# nfc-epd-afe.net
KiCad netlist of a schematic drawn in Altium Designer
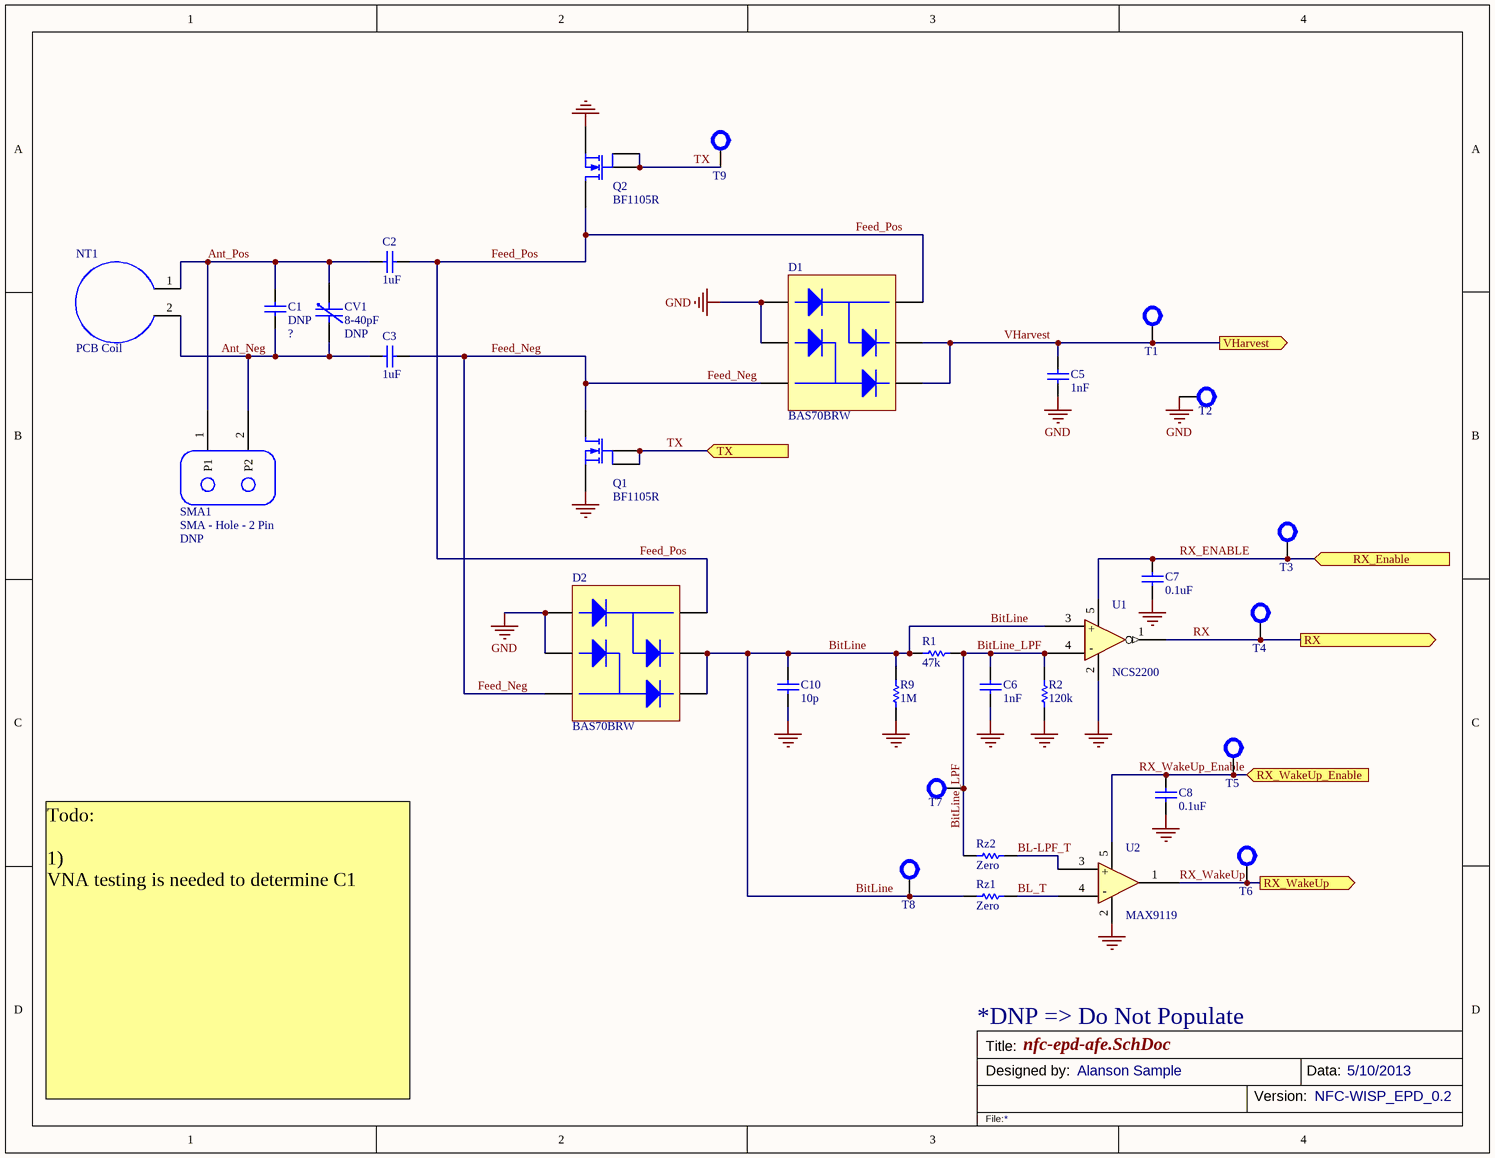
[diagram p0: nfc-epd-afe.SchDoc]

(export (version "E")
  (design (tool "Eeschema 10.0.6"))
  (components
    (comp (ref "C1")
      (value "?")
      (footprint "0603")
      (description "Ceramic Capacitor (Surface Mount)")
      (fields
        (field (name "MANUFACTURER") "Generic Ceramic Chip Cap (TBD)")
        (field (name "NOTE") "DNP")
        (field (name "Comment") "Cap")
      )
      (libsource (lib "WISP_AD10") (part "Cap"))
    )
    (comp (ref "C2")
      (value "1uF")
      (footprint "0603")
      (description "Ceramic Capacitor (Surface Mount)")
      (fields (field (name "MANUFACTURER") "Generic Ceramic Chip Cap (TBD)") (field (name "Comment") "Cap"))
      (libsource (lib "WISP_AD10") (part "Cap"))
    )
    (comp (ref "C3")
      (value "1uF")
      (footprint "0603")
      (description "Ceramic Capacitor (Surface Mount)")
      (fields (field (name "MANUFACTURER") "Generic Ceramic Chip Cap (TBD)") (field (name "Comment") "Cap"))
      (libsource (lib "WISP_AD10") (part "Cap"))
    )
    (comp (ref "C5")
      (value "1nF")
      (footprint "0603")
      (description "Ceramic Capacitor (Surface Mount)")
      (fields (field (name "MANUFACTURER") "Generic Ceramic Chip Cap (TBD)") (field (name "Comment") "Cap"))
      (libsource (lib "WISP_AD10") (part "Cap"))
    )
    (comp (ref "C6")
      (value "1nF")
      (footprint "0603")
      (description "Ceramic Capacitor (Surface Mount)")
      (fields (field (name "MANUFACTURER") "Generic Ceramic Chip Cap (TBD)") (field (name "Comment") "Cap"))
      (libsource (lib "WISP_AD10") (part "Cap"))
    )
    (comp (ref "C7")
      (value "0.1uF")
      (footprint "0603")
      (description "Ceramic Capacitor (Surface Mount)")
      (fields (field (name "MANUFACTURER") "Generic Ceramic Chip Cap (TBD)") (field (name "Comment") "Cap"))
      (libsource (lib "WISP_AD10") (part "Cap"))
    )
    (comp (ref "C8")
      (value "0.1uF")
      (footprint "0603")
      (description "Ceramic Capacitor (Surface Mount)")
      (fields (field (name "MANUFACTURER") "Generic Ceramic Chip Cap (TBD)") (field (name "Comment") "Cap"))
      (libsource (lib "WISP_AD10") (part "Cap"))
    )
    (comp (ref "C10")
      (value "10p")
      (footprint "0603")
      (description "Ceramic Capacitor (Surface Mount)")
      (fields (field (name "MANUFACTURER") "Generic Ceramic Chip Cap (TBD)") (field (name "Comment") "Cap"))
      (libsource (lib "WISP_AD10") (part "Cap"))
    )
    (comp (ref "CV1")
      (value "8-40pF")
      (footprint "Var-Cap - GKY40056")
      (description "Var-Cap Sprague-Goodman GKY40056")
      (fields
        (field (name "DIGI-KEY PART NUMBER") "SG9013CT-ND")
        (field (name "MANUFACTURER PART NUMBER") "GKY40056")
        (field (name "NOTES") "DNP")
      )
      (libsource (lib "WISP_AD10") (part "Var-Cap/603"))
    )
    (comp (ref "D1")
      (value "BAS70BRW")
      (footprint "SOT-363")
      (description "Diode Array - 2 Pair Series Connection")
      (fields
        (field (name "MANUFACTURER") "Diodes Inc")
        (field (name "MANUFACTURER PART NUMBER") "BAS70BRW-7-F")
      )
      (libsource (lib "WISP_AD10") (part "Diode - Array_2"))
    )
    (comp (ref "D2")
      (value "BAS70BRW")
      (footprint "SOT-363")
      (description "Diode Array - 2 Pair Series Connection")
      (fields
        (field (name "MANUFACTURER") "Diodes Inc")
        (field (name "MANUFACTURER PART NUMBER") "BAS70BRW-7-F")
      )
      (libsource (lib "WISP_AD10") (part "Diode - Array_2"))
    )
    (comp (ref "NT1")
      (value "PCB Coil")
      (footprint "Net Tie - 50mil")
      (description "Hand draw coil symbol based on a 'Net Tie'")
      (libsource (lib "WISP_AD10") (part "Net Tie - Coil"))
    )
    (comp (ref "Q1")
      (value "BF1105R")
      (footprint "SOT-143R")
      (description "SOT-143R, N-Channel Dual-Gate Mos-Fets MOSFET")
      (fields
        (field (name "DIGI-KEY PART NUMBER") "BF1105R,215-ND")
        (field (name "MANUFACTURER PART NUMBER") "BF1105R,215")
      )
      (libsource (lib "WISP_AD10") (part "BF1105R"))
    )
    (comp (ref "Q2")
      (value "BF1105R")
      (footprint "SOT-143R")
      (description "SOT-143R, N-Channel Dual-Gate Mos-Fets MOSFET")
      (fields
        (field (name "DIGI-KEY PART NUMBER") "BF1105R,215-ND")
        (field (name "MANUFACTURER PART NUMBER") "BF1105R,215")
      )
      (libsource (lib "WISP_AD10") (part "BF1105R"))
    )
    (comp (ref "R1")
      (value "47k")
      (footprint "0603")
      (description "Chip Resistor (Surface Mount)")
      (fields (field (name "MANUFACTURER") "Generic Chip Res (TBD)") (field (name "Comment") "Res"))
      (libsource (lib "WISP_AD10") (part "Res"))
    )
    (comp (ref "R2")
      (value "120k")
      (footprint "0603")
      (description "Chip Resistor (Surface Mount)")
      (fields (field (name "MANUFACTURER") "Generic Chip Res (TBD)") (field (name "Comment") "Res"))
      (libsource (lib "WISP_AD10") (part "Res"))
    )
    (comp (ref "R9")
      (value "1M")
      (footprint "0603")
      (description "Chip Resistor (Surface Mount)")
      (fields (field (name "MANUFACTURER") "Generic Chip Res (TBD)") (field (name "Comment") "Res"))
      (libsource (lib "WISP_AD10") (part "Res"))
    )
    (comp (ref "Rz1")
      (value "Zero")
      (footprint "0603")
      (description "Chip Resistor (Surface Mount)")
      (fields (field (name "MANUFACTURER") "Generic Chip Res (TBD)") (field (name "Comment") "Res"))
      (libsource (lib "WREL_AD10") (part "Res"))
    )
    (comp (ref "Rz2")
      (value "Zero")
      (footprint "0603")
      (description "Chip Resistor (Surface Mount)")
      (fields (field (name "MANUFACTURER") "Generic Chip Res (TBD)") (field (name "Comment") "Res"))
      (libsource (lib "WREL_AD10") (part "Res"))
    )
    (comp (ref "SMA1")
      (value "SMA - Hole - 2 Pin")
      (footprint "SMA - Hole - 2 Pin")
      (description "Two pin SMA connector wisp")
      (fields (field (name "NOTE") "DNP"))
      (libsource (lib "WISP_AD10") (part "SMA - Hole - 2 Pin"))
    )
    (comp (ref "T1")
      (value "Test Point")
      (footprint "Test Point - Small")
      (description "Test Point, large or small foot prints")
      (fields
        (field (name "DIGI-KEY PART NUMBER") "Example: 5000K-ND, 5012K-ND, Surface mount 5015KCT-ND")
        (field (name "MANUFACTURER PART NUMBER") "Example: 5000, 5013")
      )
      (libsource (lib "WISP_AD10") (part "Test Point"))
    )
    (comp (ref "T2")
      (value "Test Point")
      (footprint "Test Point - Small")
      (description "Test Point, large or small foot prints")
      (fields
        (field (name "DIGI-KEY PART NUMBER") "Example: 5000K-ND, 5012K-ND, Surface mount 5015KCT-ND")
        (field (name "MANUFACTURER PART NUMBER") "Example: 5000, 5013")
      )
      (libsource (lib "WISP_AD10") (part "Test Point"))
    )
    (comp (ref "T3")
      (value "Test Point")
      (footprint "Test Point - Small")
      (description "Test Point, large or small foot prints")
      (fields
        (field (name "DIGI-KEY PART NUMBER") "Example: 5000K-ND, 5012K-ND, Surface mount 5015KCT-ND")
        (field (name "MANUFACTURER PART NUMBER") "Example: 5000, 5013")
      )
      (libsource (lib "WISP_AD10") (part "Test Point"))
    )
    (comp (ref "T4")
      (value "Test Point")
      (footprint "Test Point - Small")
      (description "Test Point, large or small foot prints")
      (fields
        (field (name "DIGI-KEY PART NUMBER") "Example: 5000K-ND, 5012K-ND, Surface mount 5015KCT-ND")
        (field (name "MANUFACTURER PART NUMBER") "Example: 5000, 5013")
      )
      (libsource (lib "WISP_AD10") (part "Test Point"))
    )
    (comp (ref "T5")
      (value "Test Point")
      (footprint "Test Point - Small")
      (description "Test Point, large or small foot prints")
      (fields
        (field (name "DIGI-KEY PART NUMBER") "Example: 5000K-ND, 5012K-ND, Surface mount 5015KCT-ND")
        (field (name "MANUFACTURER PART NUMBER") "Example: 5000, 5013")
      )
      (libsource (lib "WISP_AD10") (part "Test Point"))
    )
    (comp (ref "T6")
      (value "Test Point")
      (footprint "Test Point - Small")
      (description "Test Point, large or small foot prints")
      (fields
        (field (name "DIGI-KEY PART NUMBER") "Example: 5000K-ND, 5012K-ND, Surface mount 5015KCT-ND")
        (field (name "MANUFACTURER PART NUMBER") "Example: 5000, 5013")
      )
      (libsource (lib "WISP_AD10") (part "Test Point"))
    )
    (comp (ref "T7")
      (value "Test Point")
      (footprint "Test Point - Small")
      (description "Test Point, large or small foot prints")
      (fields
        (field (name "DIGI-KEY PART NUMBER") "Example: 5000K-ND, 5012K-ND, Surface mount 5015KCT-ND")
        (field (name "MANUFACTURER PART NUMBER") "Example: 5000, 5013")
      )
      (libsource (lib "WISP_AD10") (part "Test Point"))
    )
    (comp (ref "T8")
      (value "Test Point")
      (footprint "Test Point - Small")
      (description "Test Point, large or small foot prints")
      (fields
        (field (name "DIGI-KEY PART NUMBER") "Example: 5000K-ND, 5012K-ND, Surface mount 5015KCT-ND")
        (field (name "MANUFACTURER PART NUMBER") "Example: 5000, 5013")
      )
      (libsource (lib "WISP_AD10") (part "Test Point"))
    )
    (comp (ref "T9")
      (value "Test Point")
      (footprint "Test Point - Small")
      (description "Test Point, large or small foot prints")
      (fields
        (field (name "DIGI-KEY PART NUMBER") "Example: 5000K-ND, 5012K-ND, Surface mount 5015KCT-ND")
        (field (name "MANUFACTURER PART NUMBER") "Example: 5000, 5013")
      )
      (libsource (lib "WISP_AD10") (part "Test Point"))
    )
    (comp (ref "U1")
      (value "NCS2200")
      (footprint "SC70-5")
      (description "Comparator: On Semi 10uA Comparator")
      (fields
        (field (name "DIGI-KEY PART NUMBER") "NCS2200SQ2T2GOSTR-ND")
        (field (name "MANUFACTURER") "ON Semiconductor")
      )
      (libsource (lib "WISP_AD10") (part "NCS2200"))
    )
    (comp (ref "U2")
      (value "MAX9119")
      (footprint "SC70-5")
      (description "IC COMPARATOR BTR SC70-5, 350nA")
      (fields
        (field (name "DIGI-KEY PART NUMBER") "MAX9119EXK+TCT-ND")
        (field (name "MANUFACTURER") "Maxim Integrated")
      )
      (libsource (lib "WISP_AD10") (part "MAX9119"))
    )
  )
  (nets
    (net (code "1") (name "/Ant_Neg") (class "Default")
      (node (ref "C1") (pin "2") (pinfunction "2_2") (pintype "passive"))
      (node (ref "C3") (pin "1") (pinfunction "1_1") (pintype "passive"))
      (node (ref "CV1") (pin "2") (pinfunction "2_2") (pintype "passive"))
      (node (ref "NT1") (pin "2") (pinfunction "N2_2") (pintype "passive"))
      (node (ref "SMA1") (pin "2") (pinfunction "P2_2") (pintype "passive"))
    )
    (net (code "2") (name "/Ant_Pos") (class "Default")
      (node (ref "C1") (pin "1") (pinfunction "1_1") (pintype "passive"))
      (node (ref "C2") (pin "1") (pinfunction "1_1") (pintype "passive"))
      (node (ref "CV1") (pin "1") (pinfunction "1_1") (pintype "passive"))
      (node (ref "NT1") (pin "1") (pinfunction "N1_1") (pintype "passive"))
      (node (ref "SMA1") (pin "1") (pinfunction "P1_1") (pintype "passive"))
    )
    (net (code "3") (name "/BL-LPF_T") (class "Default")
      (node (ref "Rz2") (pin "2") (pinfunction "2_2") (pintype "passive"))
      (node (ref "U2") (pin "3") (pinfunction "IN+_3") (pintype "passive"))
    )
    (net (code "4") (name "/BL_T") (class "Default")
      (node (ref "Rz1") (pin "2") (pinfunction "2_2") (pintype "passive"))
      (node (ref "U2") (pin "4") (pinfunction "In-_4") (pintype "passive"))
    )
    (net (code "5") (name "/BitLine") (class "Default")
      (node (ref "C10") (pin "1") (pinfunction "1_1") (pintype "passive"))
      (node (ref "D2") (pin "4") (pinfunction "C2_4") (pintype "passive"))
      (node (ref "D2") (pin "5") (pinfunction "C1_5") (pintype "passive"))
      (node (ref "R1") (pin "1") (pinfunction "1_1") (pintype "passive"))
      (node (ref "R9") (pin "1") (pinfunction "1_1") (pintype "passive"))
      (node (ref "Rz1") (pin "1") (pinfunction "1_1") (pintype "passive"))
      (node (ref "T8") (pin "0") (pinfunction "0_0") (pintype "passive"))
      (node (ref "U1") (pin "3") (pinfunction "IN+_3") (pintype "passive"))
    )
    (net (code "6") (name "/BitLine_LPF") (class "Default")
      (node (ref "C6") (pin "1") (pinfunction "1_1") (pintype "passive"))
      (node (ref "R1") (pin "2") (pinfunction "2_2") (pintype "passive"))
      (node (ref "R2") (pin "1") (pinfunction "1_1") (pintype "passive"))
      (node (ref "Rz2") (pin "1") (pinfunction "1_1") (pintype "passive"))
      (node (ref "T7") (pin "0") (pinfunction "0_0") (pintype "passive"))
      (node (ref "U1") (pin "4") (pinfunction "In-_4") (pintype "passive"))
    )
    (net (code "7") (name "/Feed_Neg") (class "Default")
      (node (ref "C3") (pin "2") (pinfunction "2_2") (pintype "passive"))
      (node (ref "D1") (pin "3") (pinfunction "AC2_3") (pintype "passive"))
      (node (ref "D2") (pin "3") (pinfunction "AC2_3") (pintype "passive"))
      (node (ref "Q1") (pin "2") (pinfunction "D_2") (pintype "passive"))
    )
    (net (code "8") (name "/Feed_Pos") (class "Default")
      (node (ref "C2") (pin "2") (pinfunction "2_2") (pintype "passive"))
      (node (ref "D1") (pin "6") (pinfunction "AC1_6") (pintype "passive"))
      (node (ref "D2") (pin "6") (pinfunction "AC1_6") (pintype "passive"))
      (node (ref "Q2") (pin "2") (pinfunction "D_2") (pintype "passive"))
    )
    (net (code "9") (name "/RX") (class "Default")
      (node (ref "T4") (pin "0") (pinfunction "0_0") (pintype "passive"))
      (node (ref "U1") (pin "1") (pinfunction "OUT_1") (pintype "output"))
    )
    (net (code "10") (name "/RX_ENABLE") (class "Default")
      (node (ref "C7") (pin "1") (pinfunction "1_1") (pintype "passive"))
      (node (ref "T3") (pin "0") (pinfunction "0_0") (pintype "passive"))
      (node (ref "U1") (pin "5") (pinfunction "VDD_5") (pintype "passive"))
    )
    (net (code "11") (name "/RX_WakeUp") (class "Default")
      (node (ref "T6") (pin "0") (pinfunction "0_0") (pintype "passive"))
      (node (ref "U2") (pin "1") (pinfunction "OUT_1") (pintype "passive"))
    )
    (net (code "12") (name "/RX_WakeUp_Enable") (class "Default")
      (node (ref "C8") (pin "1") (pinfunction "1_1") (pintype "passive"))
      (node (ref "T5") (pin "0") (pinfunction "0_0") (pintype "passive"))
      (node (ref "U2") (pin "5") (pinfunction "VCC_5") (pintype "passive"))
    )
    (net (code "13") (name "/TX") (class "Default")
      (node (ref "Q1") (pin "3") (pinfunction "G_3") (pintype "passive"))
      (node (ref "Q1") (pin "4") (pinfunction "G_4") (pintype "passive"))
      (node (ref "Q2") (pin "3") (pinfunction "G_3") (pintype "passive"))
      (node (ref "Q2") (pin "4") (pinfunction "G_4") (pintype "passive"))
      (node (ref "T9") (pin "0") (pinfunction "0_0") (pintype "passive"))
    )
    (net (code "14") (name "/VHarvest") (class "Default")
      (node (ref "C5") (pin "1") (pinfunction "1_1") (pintype "passive"))
      (node (ref "D1") (pin "4") (pinfunction "C2_4") (pintype "passive"))
      (node (ref "D1") (pin "5") (pinfunction "C1_5") (pintype "passive"))
      (node (ref "T1") (pin "0") (pinfunction "0_0") (pintype "passive"))
    )
    (net (code "15") (name "GND") (class "Default")
      (node (ref "C10") (pin "2") (pinfunction "2_2") (pintype "passive"))
      (node (ref "C5") (pin "2") (pinfunction "2_2") (pintype "passive"))
      (node (ref "C6") (pin "2") (pinfunction "2_2") (pintype "passive"))
      (node (ref "C7") (pin "2") (pinfunction "2_2") (pintype "passive"))
      (node (ref "C8") (pin "2") (pinfunction "2_2") (pintype "passive"))
      (node (ref "D1") (pin "1") (pinfunction "A1_1") (pintype "passive"))
      (node (ref "D1") (pin "2") (pinfunction "A2_2") (pintype "passive"))
      (node (ref "D2") (pin "1") (pinfunction "A1_1") (pintype "passive"))
      (node (ref "D2") (pin "2") (pinfunction "A2_2") (pintype "passive"))
      (node (ref "Q1") (pin "1") (pinfunction "S_1") (pintype "passive"))
      (node (ref "Q2") (pin "1") (pinfunction "S_1") (pintype "passive"))
      (node (ref "R2") (pin "2") (pinfunction "2_2") (pintype "passive"))
      (node (ref "R9") (pin "2") (pinfunction "2_2") (pintype "passive"))
      (node (ref "T2") (pin "0") (pinfunction "0_0") (pintype "passive"))
      (node (ref "U1") (pin "2") (pinfunction "Gnd_2") (pintype "power_in"))
      (node (ref "U2") (pin "2") (pinfunction "VEE_2") (pintype "passive"))
    )
  )
)
